# 27C160_Adapter.net
KiCad netlist of a schematic drawn in EAGLE
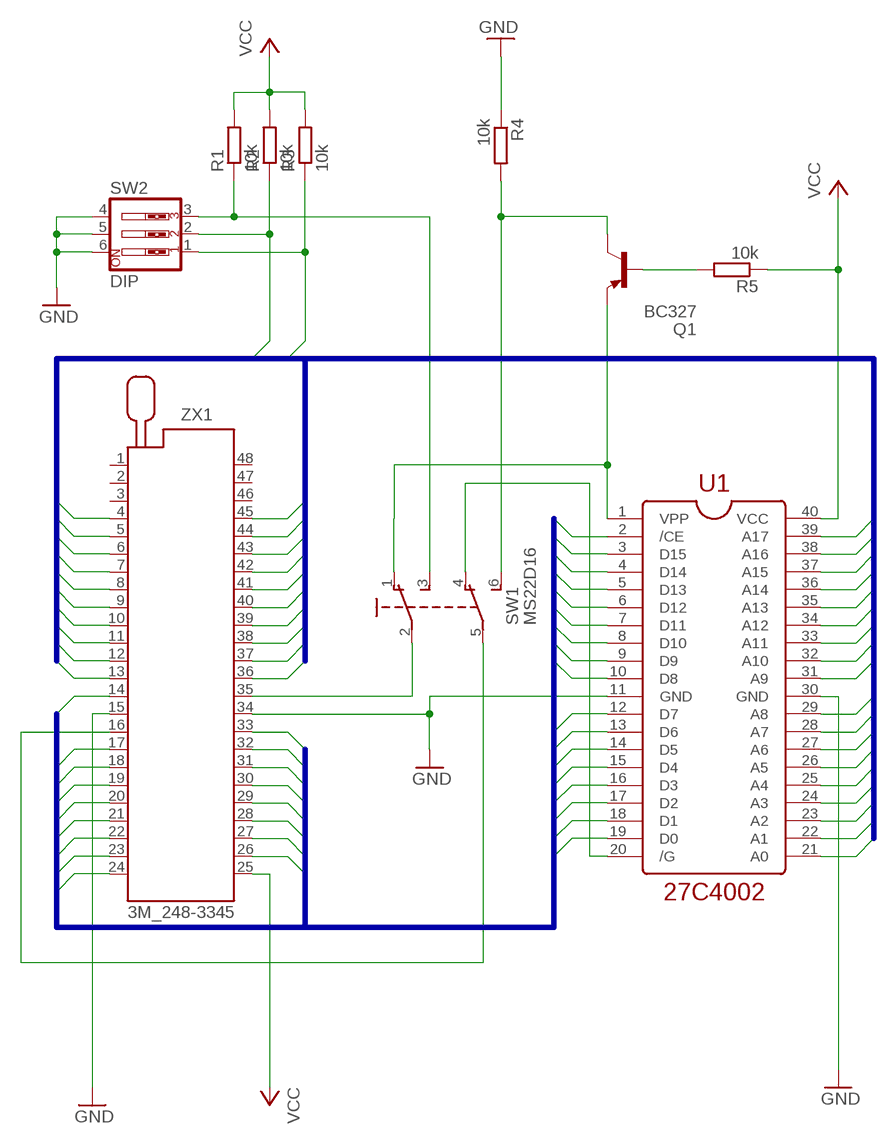
[diagram p0: schematic, sheet 1]

(export (version "E")
  (design (tool "Eeschema 10.0.6"))
  (components
    (comp (ref "Q1")
      (value "BC327")
      (footprint "eagle-import:TO92-EBC")
      (libsource (lib "eagle-import") (part "BC327"))
    )
    (comp (ref "R1")
      (value "10k")
      (footprint "eagle-import:0207_10")
      (libsource (lib "eagle-import") (part "R-EU_0207/10"))
    )
    (comp (ref "R2")
      (value "10k")
      (footprint "eagle-import:0207_10")
      (libsource (lib "eagle-import") (part "R-EU_0207/10"))
    )
    (comp (ref "R3")
      (value "10k")
      (footprint "eagle-import:0207_10")
      (libsource (lib "eagle-import") (part "R-EU_0207/10"))
    )
    (comp (ref "R4")
      (value "10k")
      (footprint "eagle-import:0207_10")
      (libsource (lib "eagle-import") (part "R-EU_0207/10"))
    )
    (comp (ref "R5")
      (value "10k")
      (footprint "eagle-import:0207_10")
      (libsource (lib "eagle-import") (part "R-EU_0207/10"))
    )
    (comp (ref "SW1")
      (value "MS22D16")
      (footprint "eagle-import:MS22D16")
      (libsource (lib "eagle-import") (part "MS22D16"))
    )
    (comp (ref "SW2")
      (value "DIP")
      (footprint "eagle-import:EDG-03")
      (libsource (lib "eagle-import") (part "SW_DIP-3"))
    )
    (comp (ref "U1")
      (value "27C4002")
      (footprint "eagle-import:27C4002")
      (libsource (lib "eagle-import") (part "27C4002"))
    )
    (comp (ref "ZX1")
      (value "3M_248-3345")
      (footprint "eagle-import:3M_248-3345")
      (fields (field (name "MF") "3M") (field (name "MPN") "248-1282-00-0602J"))
      (libsource (lib "eagle-import") (part "3M_248-3345"))
    )
  )
  (nets
    (net (code "1") (name "/A0") (class "Default")
      (node (ref "U1") (pin "21") (pinfunction "A0_21") (pintype "bidirectional"))
      (node (ref "ZX1") (pin "13") (pinfunction "13_13") (pintype "passive"))
    )
    (net (code "2") (name "/A1") (class "Default")
      (node (ref "U1") (pin "22") (pinfunction "A1_22") (pintype "bidirectional"))
      (node (ref "ZX1") (pin "12") (pinfunction "12_12") (pintype "passive"))
    )
    (net (code "3") (name "/A2") (class "Default")
      (node (ref "U1") (pin "23") (pinfunction "A2_23") (pintype "bidirectional"))
      (node (ref "ZX1") (pin "11") (pinfunction "11_11") (pintype "passive"))
    )
    (net (code "4") (name "/A3") (class "Default")
      (node (ref "U1") (pin "24") (pinfunction "A3_24") (pintype "bidirectional"))
      (node (ref "ZX1") (pin "10") (pinfunction "10_10") (pintype "passive"))
    )
    (net (code "5") (name "/A4") (class "Default")
      (node (ref "U1") (pin "25") (pinfunction "A4_25") (pintype "bidirectional"))
      (node (ref "ZX1") (pin "9") (pinfunction "9_9") (pintype "passive"))
    )
    (net (code "6") (name "/A5") (class "Default")
      (node (ref "U1") (pin "26") (pinfunction "A5_26") (pintype "bidirectional"))
      (node (ref "ZX1") (pin "8") (pinfunction "8_8") (pintype "passive"))
    )
    (net (code "7") (name "/A6") (class "Default")
      (node (ref "U1") (pin "27") (pinfunction "A6_27") (pintype "bidirectional"))
      (node (ref "ZX1") (pin "7") (pinfunction "7_7") (pintype "passive"))
    )
    (net (code "8") (name "/A7") (class "Default")
      (node (ref "U1") (pin "28") (pinfunction "A7_28") (pintype "bidirectional"))
      (node (ref "ZX1") (pin "6") (pinfunction "6_6") (pintype "passive"))
    )
    (net (code "9") (name "/A8") (class "Default")
      (node (ref "U1") (pin "29") (pinfunction "A8_29") (pintype "bidirectional"))
      (node (ref "ZX1") (pin "44") (pinfunction "44_44") (pintype "passive"))
    )
    (net (code "10") (name "/A9") (class "Default")
      (node (ref "U1") (pin "31") (pinfunction "A9_31") (pintype "bidirectional"))
      (node (ref "ZX1") (pin "43") (pinfunction "43_43") (pintype "passive"))
    )
    (net (code "11") (name "/A10") (class "Default")
      (node (ref "U1") (pin "32") (pinfunction "A10_32") (pintype "bidirectional"))
      (node (ref "ZX1") (pin "42") (pinfunction "42_42") (pintype "passive"))
    )
    (net (code "12") (name "/A11") (class "Default")
      (node (ref "U1") (pin "33") (pinfunction "A11_33") (pintype "bidirectional"))
      (node (ref "ZX1") (pin "41") (pinfunction "41_41") (pintype "passive"))
    )
    (net (code "13") (name "/A12") (class "Default")
      (node (ref "U1") (pin "34") (pinfunction "A12_34") (pintype "bidirectional"))
      (node (ref "ZX1") (pin "40") (pinfunction "40_40") (pintype "passive"))
    )
    (net (code "14") (name "/A13") (class "Default")
      (node (ref "U1") (pin "35") (pinfunction "A13_35") (pintype "bidirectional"))
      (node (ref "ZX1") (pin "39") (pinfunction "39_39") (pintype "passive"))
    )
    (net (code "15") (name "/A14") (class "Default")
      (node (ref "U1") (pin "36") (pinfunction "A14_36") (pintype "bidirectional"))
      (node (ref "ZX1") (pin "38") (pinfunction "38_38") (pintype "passive"))
    )
    (net (code "16") (name "/A15") (class "Default")
      (node (ref "U1") (pin "37") (pinfunction "A15_37") (pintype "bidirectional"))
      (node (ref "ZX1") (pin "37") (pinfunction "37_37") (pintype "passive"))
    )
    (net (code "17") (name "/A16") (class "Default")
      (node (ref "U1") (pin "38") (pinfunction "A16_38") (pintype "bidirectional"))
      (node (ref "ZX1") (pin "36") (pinfunction "36_36") (pintype "passive"))
    )
    (net (code "18") (name "/A17") (class "Default")
      (node (ref "U1") (pin "39") (pinfunction "A17_39") (pintype "bidirectional"))
      (node (ref "ZX1") (pin "5") (pinfunction "5_5") (pintype "passive"))
    )
    (net (code "19") (name "/A18") (class "Default")
      (node (ref "R3") (pin "1") (pinfunction "1_1") (pintype "passive"))
      (node (ref "SW2") (pin "1") (pinfunction "1_1") (pintype "passive"))
      (node (ref "ZX1") (pin "4") (pinfunction "4_4") (pintype "passive"))
    )
    (net (code "20") (name "/A19") (class "Default")
      (node (ref "R2") (pin "1") (pinfunction "1_1") (pintype "passive"))
      (node (ref "SW2") (pin "2") (pinfunction "2_2") (pintype "passive"))
      (node (ref "ZX1") (pin "45") (pinfunction "45_45") (pintype "passive"))
    )
    (net (code "21") (name "/D0") (class "Default")
      (node (ref "U1") (pin "19") (pinfunction "D0_19") (pintype "bidirectional"))
      (node (ref "ZX1") (pin "17") (pinfunction "17_17") (pintype "passive"))
    )
    (net (code "22") (name "/D1") (class "Default")
      (node (ref "U1") (pin "18") (pinfunction "D1_18") (pintype "bidirectional"))
      (node (ref "ZX1") (pin "19") (pinfunction "19_19") (pintype "passive"))
    )
    (net (code "23") (name "/D2") (class "Default")
      (node (ref "U1") (pin "17") (pinfunction "D2_17") (pintype "bidirectional"))
      (node (ref "ZX1") (pin "21") (pinfunction "21_21") (pintype "passive"))
    )
    (net (code "24") (name "/D3") (class "Default")
      (node (ref "U1") (pin "16") (pinfunction "D3_16") (pintype "bidirectional"))
      (node (ref "ZX1") (pin "23") (pinfunction "23_23") (pintype "passive"))
    )
    (net (code "25") (name "/D4") (class "Default")
      (node (ref "U1") (pin "15") (pinfunction "D4_15") (pintype "bidirectional"))
      (node (ref "ZX1") (pin "26") (pinfunction "26_26") (pintype "passive"))
    )
    (net (code "26") (name "/D5") (class "Default")
      (node (ref "U1") (pin "14") (pinfunction "D5_14") (pintype "bidirectional"))
      (node (ref "ZX1") (pin "28") (pinfunction "28_28") (pintype "passive"))
    )
    (net (code "27") (name "/D6") (class "Default")
      (node (ref "U1") (pin "13") (pinfunction "D6_13") (pintype "bidirectional"))
      (node (ref "ZX1") (pin "30") (pinfunction "30_30") (pintype "passive"))
    )
    (net (code "28") (name "/D7") (class "Default")
      (node (ref "U1") (pin "12") (pinfunction "D7_12") (pintype "bidirectional"))
      (node (ref "ZX1") (pin "32") (pinfunction "32_32") (pintype "passive"))
    )
    (net (code "29") (name "/D8") (class "Default")
      (node (ref "U1") (pin "10") (pinfunction "D8_10") (pintype "bidirectional"))
      (node (ref "ZX1") (pin "18") (pinfunction "18_18") (pintype "passive"))
    )
    (net (code "30") (name "/D9") (class "Default")
      (node (ref "U1") (pin "9") (pinfunction "D9_9") (pintype "bidirectional"))
      (node (ref "ZX1") (pin "20") (pinfunction "20_20") (pintype "passive"))
    )
    (net (code "31") (name "/D10") (class "Default")
      (node (ref "U1") (pin "8") (pinfunction "D10_8") (pintype "bidirectional"))
      (node (ref "ZX1") (pin "22") (pinfunction "22_22") (pintype "passive"))
    )
    (net (code "32") (name "/D11") (class "Default")
      (node (ref "U1") (pin "7") (pinfunction "D11_7") (pintype "bidirectional"))
      (node (ref "ZX1") (pin "24") (pinfunction "24_24") (pintype "passive"))
    )
    (net (code "33") (name "/D12") (class "Default")
      (node (ref "U1") (pin "6") (pinfunction "D12_6") (pintype "bidirectional"))
      (node (ref "ZX1") (pin "27") (pinfunction "27_27") (pintype "passive"))
    )
    (net (code "34") (name "/D13") (class "Default")
      (node (ref "U1") (pin "5") (pinfunction "D13_5") (pintype "bidirectional"))
      (node (ref "ZX1") (pin "29") (pinfunction "29_29") (pintype "passive"))
    )
    (net (code "35") (name "/D14") (class "Default")
      (node (ref "U1") (pin "4") (pinfunction "D14_4") (pintype "bidirectional"))
      (node (ref "ZX1") (pin "31") (pinfunction "31_31") (pintype "passive"))
    )
    (net (code "36") (name "/D15") (class "Default")
      (node (ref "U1") (pin "3") (pinfunction "D15_3") (pintype "bidirectional"))
      (node (ref "ZX1") (pin "33") (pinfunction "33_33") (pintype "passive"))
    )
    (net (code "37") (name "/E") (class "Default")
      (node (ref "U1") (pin "2") (pinfunction "/CE_2") (pintype "bidirectional"))
      (node (ref "ZX1") (pin "14") (pinfunction "14_14") (pintype "passive"))
    )
    (net (code "38") (name "GND") (class "Default")
      (node (ref "R4") (pin "1") (pinfunction "1_1") (pintype "passive"))
      (node (ref "SW2") (pin "4") (pinfunction "4_4") (pintype "passive"))
      (node (ref "SW2") (pin "5") (pinfunction "5_5") (pintype "passive"))
      (node (ref "SW2") (pin "6") (pinfunction "6_6") (pintype "passive"))
      (node (ref "U1") (pin "11") (pinfunction "GND_11") (pintype "bidirectional"))
      (node (ref "U1") (pin "30") (pinfunction "GND_30") (pintype "bidirectional"))
      (node (ref "ZX1") (pin "15") (pinfunction "15_15") (pintype "passive"))
      (node (ref "ZX1") (pin "34") (pinfunction "34_34") (pintype "passive"))
    )
    (net (code "39") (name "Net-(Q1-PadB)") (class "Default")
      (node (ref "Q1") (pin "B") (pinfunction "B_B") (pintype "passive"))
      (node (ref "R5") (pin "2") (pinfunction "2_2") (pintype "passive"))
    )
    (net (code "40") (name "Net-(SW1-O)") (class "Default")
      (node (ref "Q1") (pin "E") (pinfunction "E_E") (pintype "passive"))
      (node (ref "SW1") (pin "1") (pinfunction "O_1") (pintype "passive"))
      (node (ref "U1") (pin "1") (pinfunction "VPP_1") (pintype "bidirectional"))
    )
    (net (code "41") (name "Net-(SW1-O1)") (class "Default")
      (node (ref "SW1") (pin "4") (pinfunction "O1_4") (pintype "passive"))
      (node (ref "U1") (pin "20") (pinfunction "/G_20") (pintype "bidirectional"))
    )
    (net (code "42") (name "Net-(SW1-P)") (class "Default")
      (node (ref "SW1") (pin "2") (pinfunction "P_2") (pintype "passive"))
      (node (ref "ZX1") (pin "35") (pinfunction "35_35") (pintype "passive"))
    )
    (net (code "43") (name "Net-(SW1-P1)") (class "Default")
      (node (ref "SW1") (pin "5") (pinfunction "P1_5") (pintype "passive"))
      (node (ref "ZX1") (pin "16") (pinfunction "16_16") (pintype "passive"))
    )
    (net (code "44") (name "Net-(SW1-S)") (class "Default")
      (node (ref "R1") (pin "1") (pinfunction "1_1") (pintype "passive"))
      (node (ref "SW1") (pin "3") (pinfunction "S_3") (pintype "passive"))
      (node (ref "SW2") (pin "3") (pinfunction "3_3") (pintype "passive"))
    )
    (net (code "45") (name "Net-(SW1-S1)") (class "Default")
      (node (ref "Q1") (pin "C") (pinfunction "C_C") (pintype "passive"))
      (node (ref "R4") (pin "2") (pinfunction "2_2") (pintype "passive"))
      (node (ref "SW1") (pin "6") (pinfunction "S1_6") (pintype "passive"))
    )
    (net (code "46") (name "VCC") (class "Default")
      (node (ref "R1") (pin "2") (pinfunction "2_2") (pintype "passive"))
      (node (ref "R2") (pin "2") (pinfunction "2_2") (pintype "passive"))
      (node (ref "R3") (pin "2") (pinfunction "2_2") (pintype "passive"))
      (node (ref "R5") (pin "1") (pinfunction "1_1") (pintype "passive"))
      (node (ref "U1") (pin "40") (pinfunction "VCC_40") (pintype "bidirectional"))
      (node (ref "ZX1") (pin "25") (pinfunction "25_25") (pintype "passive"))
    )
    (net (code "47") (name "unconnected-(ZX1-Pad1)") (class "Default")
      (node (ref "ZX1") (pin "1") (pinfunction "1_1") (pintype "passive"))
    )
    (net (code "48") (name "unconnected-(ZX1-Pad2)") (class "Default")
      (node (ref "ZX1") (pin "2") (pinfunction "2_2") (pintype "passive"))
    )
    (net (code "49") (name "unconnected-(ZX1-Pad3)") (class "Default")
      (node (ref "ZX1") (pin "3") (pinfunction "3_3") (pintype "passive"))
    )
    (net (code "50") (name "unconnected-(ZX1-Pad46)") (class "Default")
      (node (ref "ZX1") (pin "46") (pinfunction "46_46") (pintype "passive"))
    )
    (net (code "51") (name "unconnected-(ZX1-Pad47)") (class "Default")
      (node (ref "ZX1") (pin "47") (pinfunction "47_47") (pintype "passive"))
    )
    (net (code "52") (name "unconnected-(ZX1-Pad48)") (class "Default")
      (node (ref "ZX1") (pin "48") (pinfunction "48_48") (pintype "passive"))
    )
  )
)
